# stm32f4x7v.net
KiCad netlist of a schematic drawn in Altium Designer
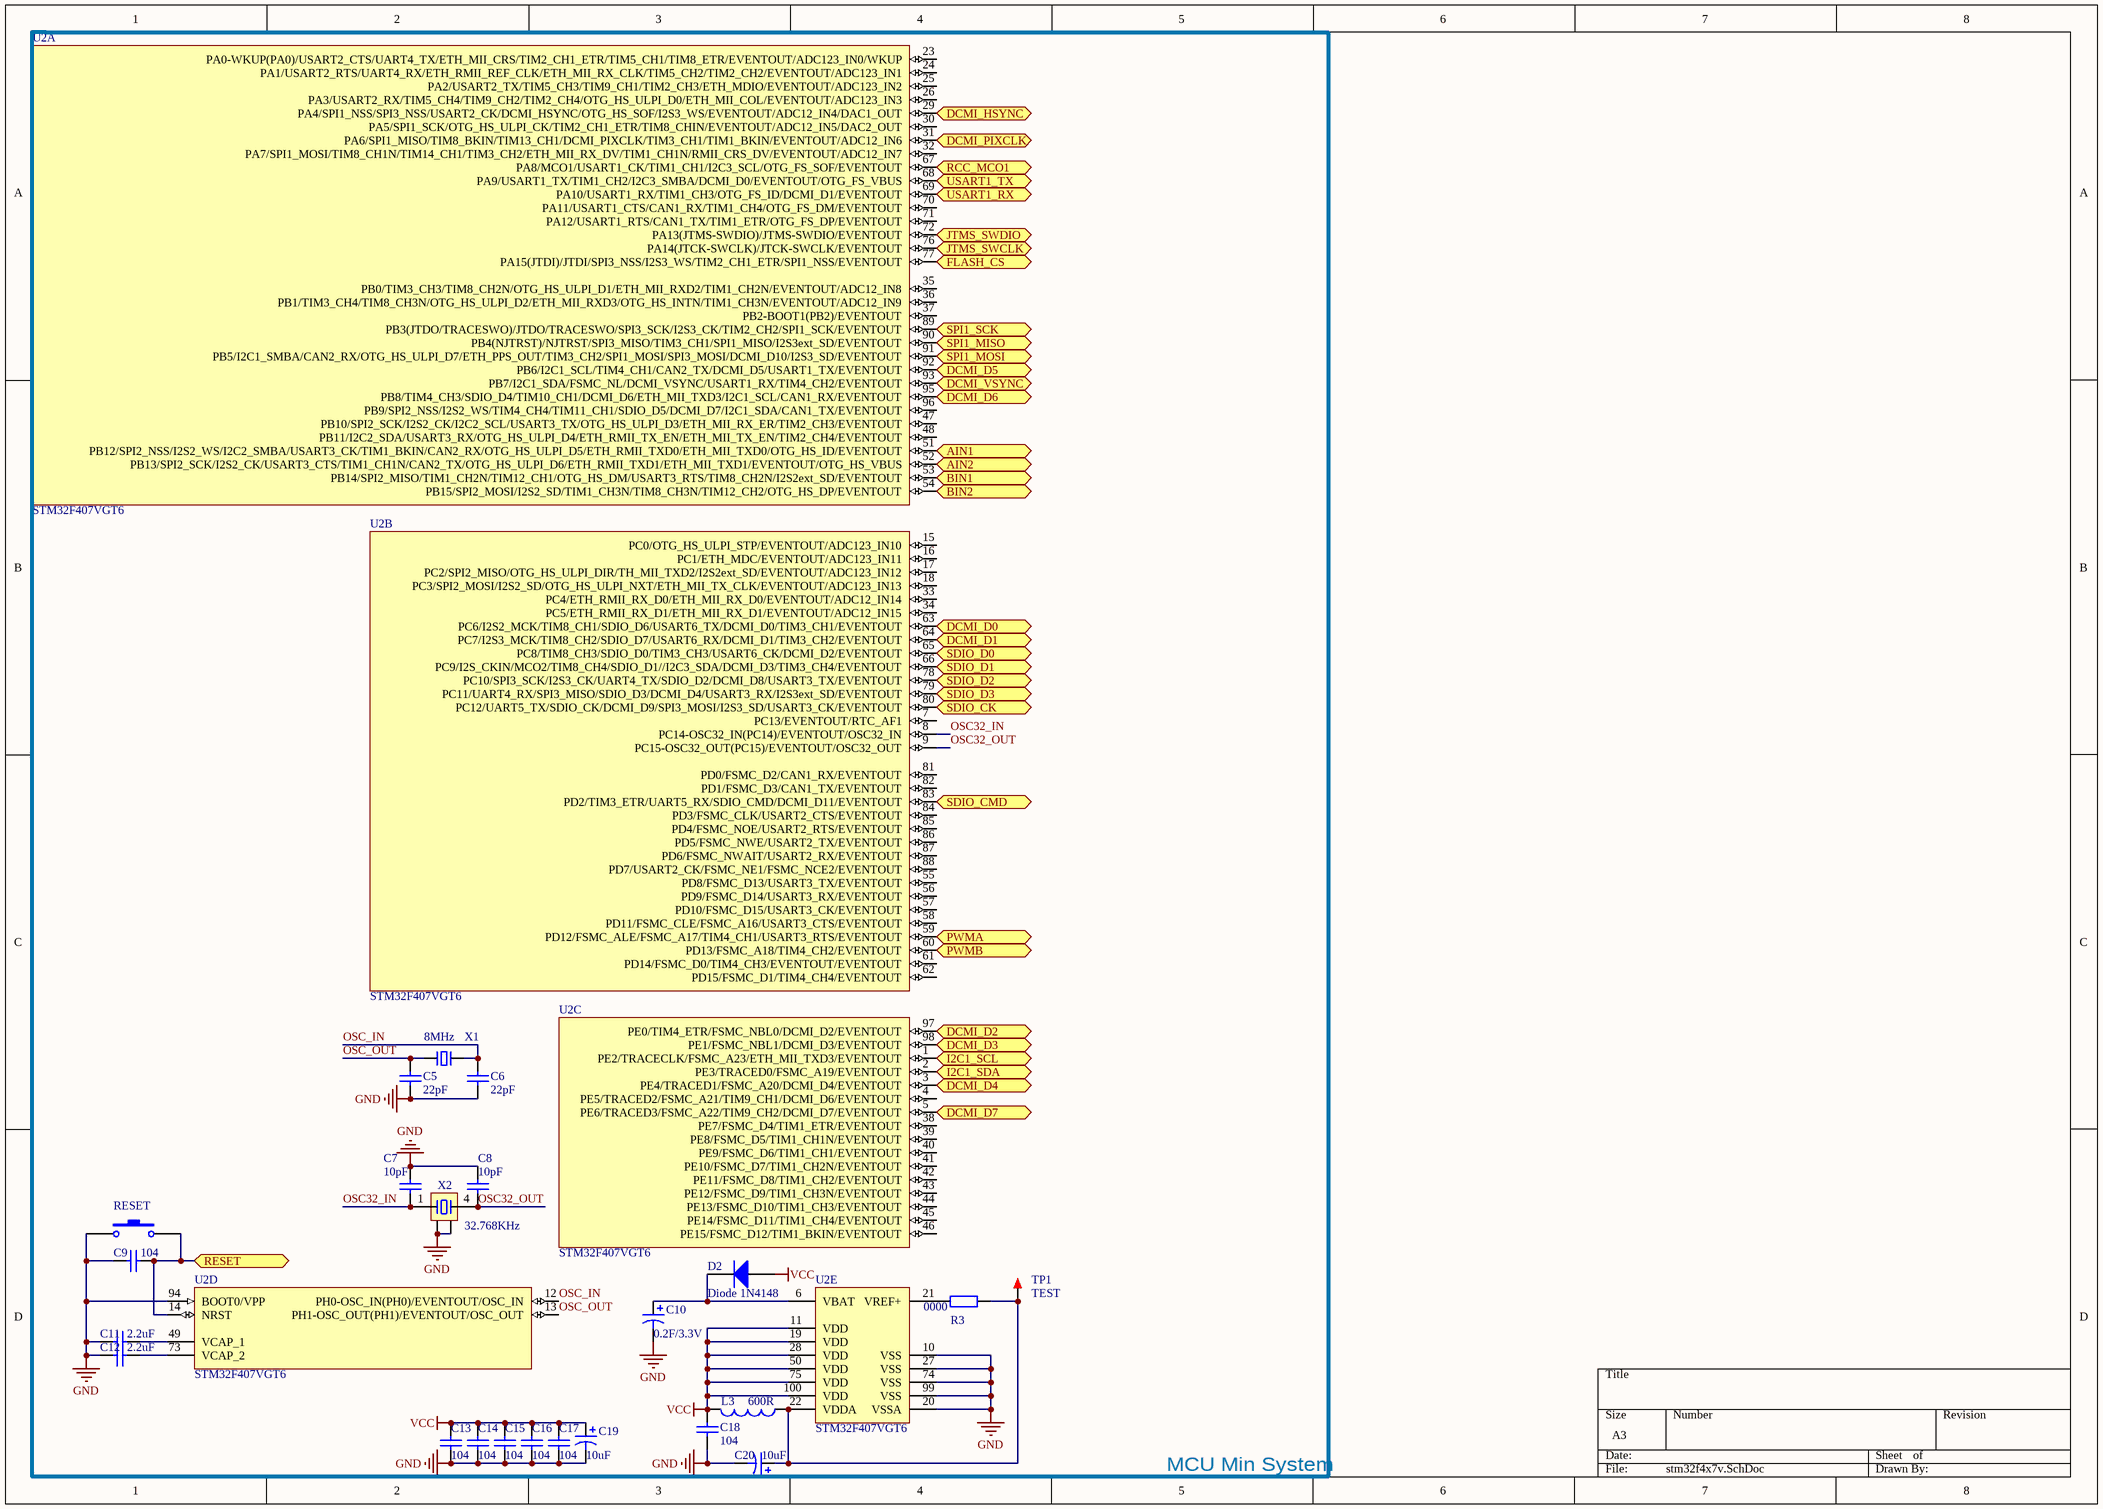
[diagram p0: stm32f4x7v.SchDoc]

(export (version "E")
  (design (tool "Eeschema 10.0.6"))
  (components
    (comp (ref "C5")
      (value "22pF")
      (footprint "C 0603_L")
      (description "Capacitor")
      (fields (field (name "PUBLISHER") "Altium Limited"))
      (libsource (lib "Miscellaneous Devices") (part "Cap"))
    )
    (comp (ref "C6")
      (value "22pF")
      (footprint "C 0603_L")
      (description "Capacitor")
      (fields (field (name "PUBLISHER") "Altium Limited"))
      (libsource (lib "Miscellaneous Devices") (part "Cap"))
    )
    (comp (ref "C7")
      (value "10pF")
      (footprint "C 0603_L")
      (description "Capacitor")
      (fields (field (name "PUBLISHER") "Altium Limited"))
      (libsource (lib "Miscellaneous Devices") (part "Cap"))
    )
    (comp (ref "C8")
      (value "10pF")
      (footprint "C 0603_L")
      (description "Capacitor")
      (fields (field (name "PUBLISHER") "Altium Limited"))
      (libsource (lib "Miscellaneous Devices") (part "Cap"))
    )
    (comp (ref "C9")
      (value "104")
      (footprint "C 0603_L")
      (description "Capacitor")
      (fields (field (name "PUBLISHER") "Altium Limited"))
      (libsource (lib "Miscellaneous Devices") (part "Cap"))
    )
    (comp (ref "C10")
      (value "0.2F/3.3V")
      (footprint "CD A(3216)")
      (description "Polarized Capacitor (Radial)")
      (fields (field (name "PUBLISHER") "Altium Limited"))
      (libsource (lib "Miscellaneous Devices") (part "Cap Pol1"))
    )
    (comp (ref "C11")
      (value "2.2uF")
      (footprint "C 0603_L")
      (description "Capacitor")
      (fields (field (name "PUBLISHER") "Altium Limited"))
      (libsource (lib "Miscellaneous Devices") (part "Cap"))
    )
    (comp (ref "C12")
      (value "2.2uF")
      (footprint "C 0603_L")
      (description "Capacitor")
      (fields (field (name "PUBLISHER") "Altium Limited"))
      (libsource (lib "Miscellaneous Devices") (part "Cap"))
    )
    (comp (ref "C13")
      (value "104")
      (footprint "C 0603_L")
      (description "Capacitor")
      (fields (field (name "PUBLISHER") "Altium Limited"))
      (libsource (lib "Miscellaneous Devices") (part "Cap"))
    )
    (comp (ref "C14")
      (value "104")
      (footprint "C 0603_L")
      (description "Capacitor")
      (fields (field (name "PUBLISHER") "Altium Limited"))
      (libsource (lib "Miscellaneous Devices") (part "Cap"))
    )
    (comp (ref "C15")
      (value "104")
      (footprint "C 0603_L")
      (description "Capacitor")
      (fields (field (name "PUBLISHER") "Altium Limited"))
      (libsource (lib "Miscellaneous Devices") (part "Cap"))
    )
    (comp (ref "C16")
      (value "104")
      (footprint "C 0603_L")
      (description "Capacitor")
      (fields (field (name "PUBLISHER") "Altium Limited"))
      (libsource (lib "Miscellaneous Devices") (part "Cap"))
    )
    (comp (ref "C17")
      (value "104")
      (footprint "C 0603_L")
      (description "Capacitor")
      (fields (field (name "PUBLISHER") "Altium Limited"))
      (libsource (lib "Miscellaneous Devices") (part "Cap"))
    )
    (comp (ref "C18")
      (value "104")
      (footprint "C 0603_L")
      (description "Capacitor")
      (fields (field (name "PUBLISHER") "Altium Limited"))
      (libsource (lib "Miscellaneous Devices") (part "Cap"))
    )
    (comp (ref "C19")
      (value "10uF")
      (footprint "CD A(3216)")
      (description "Polarized Capacitor (Radial)")
      (fields (field (name "PUBLISHER") "Altium Limited"))
      (libsource (lib "Miscellaneous Devices") (part "Cap Pol1"))
    )
    (comp (ref "C20")
      (value "10uF")
      (footprint "CD A(3216)")
      (description "Polarized Capacitor (Radial)")
      (fields (field (name "PUBLISHER") "Altium Limited"))
      (libsource (lib "Miscellaneous Devices") (part "Cap Pol1"))
    )
    (comp (ref "D2")
      (value "Diode 1N4148")
      (footprint "SOD-523")
      (description "High Conductance Fast Diode")
      (fields (field (name "PUBLISHER") "Altium Limited"))
      (libsource (lib "Miscellaneous Devices") (part "Diode 1N4148"))
    )
    (comp (ref "L3")
      (value "600R")
      (footprint "R 0603_L")
      (description "Inductor")
      (fields (field (name "PUBLISHER") "Altium Limited"))
      (libsource (lib "Miscellaneous Devices") (part "Inductor"))
    )
    (comp (ref "R3")
      (value "0000")
      (footprint "R 0603_L")
      (description "Resistor")
      (fields (field (name "PUBLISHER") "Altium Limited"))
      (libsource (lib "Miscellaneous Devices") (part "Res2"))
    )
    (comp (ref "RESET")
      (value "RESET")
      (footprint "micro button_2_SMD")
      (description "Switch")
      (fields (field (name "PUBLISHER") "Altium Limited"))
      (libsource (lib "Miscellaneous Devices") (part "SW-PB"))
    )
    (comp (ref "TP1")
      (value "TEST")
      (footprint "TEST 0.8")
      (description "测试点")
      (fields (field (name "版权归属") "源创客"))
      (libsource (lib "15.1 - 未分类器件") (part "TEST"))
    )
    (comp (ref "U2")
      (value "STM32F407VGT6")
      (footprint "LQFP100_V")
      (libsource (lib "STMicroelectronics STM32 F4") (part "STM32F407VGT6"))
    )
    (comp (ref "X1")
      (value "8MHz")
      (footprint "OSC 5032-2P")
      (description "2脚无源脚晶振")
      (fields (field (name "版权归属") "源创客"))
      (libsource (lib "10.1 - 保险丝-晶振") (part "XTAL-2P"))
    )
    (comp (ref "X2")
      (value "32.768KHz")
      (footprint "OSC MC-146")
      (description "MC系列4脚晶振")
      (fields (field (name "版权归属") "源创客"))
      (libsource (lib "10.1 - 保险丝-晶振") (part "XTAL-MC-4P"))
    )
  )
  (nets
    (net (code "1") (name "/AIN1") (class "Default")
      (node (ref "U2") (pin "51") (pinfunction "PB12/SPI2_NSS/I2S2_WS/I2C2_SMBA/USART3_CK/TIM1_BKIN/CAN2_RX/OTG_HS_ULPI_D5/ETH_RMII_TXD0/ETH_MII_TXD0/OTG_HS_ID/EVENTOUT_51") (pintype "bidirectional"))
    )
    (net (code "2") (name "/AIN2") (class "Default")
      (node (ref "U2") (pin "52") (pinfunction "PB13/SPI2_SCK/I2S2_CK/USART3_CTS/TIM1_CH1N/CAN2_TX/OTG_HS_ULPI_D6/ETH_RMII_TXD1/ETH_MII_TXD1/EVENTOUT/OTG_HS_VBUS_52") (pintype "bidirectional"))
    )
    (net (code "3") (name "/BIN1") (class "Default")
      (node (ref "U2") (pin "53") (pinfunction "PB14/SPI2_MISO/TIM1_CH2N/TIM12_CH1/OTG_HS_DM/USART3_RTS/TIM8_CH2N/I2S2ext_SD/EVENTOUT_53") (pintype "bidirectional"))
    )
    (net (code "4") (name "/BIN2") (class "Default")
      (node (ref "U2") (pin "54") (pinfunction "PB15/SPI2_MOSI/I2S2_SD/TIM1_CH3N/TIM8_CH3N/TIM12_CH2/OTG_HS_DP/EVENTOUT_54") (pintype "bidirectional"))
    )
    (net (code "5") (name "/DCMI_D0") (class "Default")
      (node (ref "U2") (pin "63") (pinfunction "PC6/I2S2_MCK/TIM8_CH1/SDIO_D6/USART6_TX/DCMI_D0/TIM3_CH1/EVENTOUT_63") (pintype "bidirectional"))
    )
    (net (code "6") (name "/DCMI_D1") (class "Default")
      (node (ref "U2") (pin "64") (pinfunction "PC7/I2S3_MCK/TIM8_CH2/SDIO_D7/USART6_RX/DCMI_D1/TIM3_CH2/EVENTOUT_64") (pintype "bidirectional"))
    )
    (net (code "7") (name "/DCMI_D2") (class "Default")
      (node (ref "U2") (pin "97") (pinfunction "PE0/TIM4_ETR/FSMC_NBL0/DCMI_D2/EVENTOUT_97") (pintype "bidirectional"))
    )
    (net (code "8") (name "/DCMI_D3") (class "Default")
      (node (ref "U2") (pin "98") (pinfunction "PE1/FSMC_NBL1/DCMI_D3/EVENTOUT_98") (pintype "bidirectional"))
    )
    (net (code "9") (name "/DCMI_D4") (class "Default")
      (node (ref "U2") (pin "3") (pinfunction "PE4/TRACED1/FSMC_A20/DCMI_D4/EVENTOUT_3") (pintype "bidirectional"))
    )
    (net (code "10") (name "/DCMI_D5") (class "Default")
      (node (ref "U2") (pin "92") (pinfunction "PB6/I2C1_SCL/TIM4_CH1/CAN2_TX/DCMI_D5/USART1_TX/EVENTOUT_92") (pintype "bidirectional"))
    )
    (net (code "11") (name "/DCMI_D6") (class "Default")
      (node (ref "U2") (pin "95") (pinfunction "PB8/TIM4_CH3/SDIO_D4/TIM10_CH1/DCMI_D6/ETH_MII_TXD3/I2C1_SCL/CAN1_RX/EVENTOUT_95") (pintype "bidirectional"))
    )
    (net (code "12") (name "/DCMI_D7") (class "Default")
      (node (ref "U2") (pin "5") (pinfunction "PE6/TRACED3/FSMC_A22/TIM9_CH2/DCMI_D7/EVENTOUT_5") (pintype "bidirectional"))
    )
    (net (code "13") (name "/DCMI_HSYNC") (class "Default")
      (node (ref "U2") (pin "29") (pinfunction "PA4/SPI1_NSS/SPI3_NSS/USART2_CK/DCMI_HSYNC/OTG_HS_SOF/I2S3_WS/EVENTOUT/ADC12_IN4/DAC1_OUT_29") (pintype "bidirectional"))
    )
    (net (code "14") (name "/DCMI_PIXCLK") (class "Default")
      (node (ref "U2") (pin "31") (pinfunction "PA6/SPI1_MISO/TIM8_BKIN/TIM13_CH1/DCMI_PIXCLK/TIM3_CH1/TIM1_BKIN/EVENTOUT/ADC12_IN6_31") (pintype "bidirectional"))
    )
    (net (code "15") (name "/DCMI_VSYNC") (class "Default")
      (node (ref "U2") (pin "93") (pinfunction "PB7/I2C1_SDA/FSMC_NL/DCMI_VSYNC/USART1_RX/TIM4_CH2/EVENTOUT_93") (pintype "bidirectional"))
    )
    (net (code "16") (name "/FLASH_CS") (class "Default")
      (node (ref "U2") (pin "77") (pinfunction "PA15(JTDI)/JTDI/SPI3_NSS/I2S3_WS/TIM2_CH1_ETR/SPI1_NSS/EVENTOUT_77") (pintype "bidirectional"))
    )
    (net (code "17") (name "/I2C1_SCL") (class "Default")
      (node (ref "U2") (pin "1") (pinfunction "PE2/TRACECLK/FSMC_A23/ETH_MII_TXD3/EVENTOUT_1") (pintype "bidirectional"))
    )
    (net (code "18") (name "/I2C1_SDA") (class "Default")
      (node (ref "U2") (pin "2") (pinfunction "PE3/TRACED0/FSMC_A19/EVENTOUT_2") (pintype "bidirectional"))
    )
    (net (code "19") (name "/JTMS_SWCLK") (class "Default")
      (node (ref "U2") (pin "76") (pinfunction "PA14(JTCK-SWCLK)/JTCK-SWCLK/EVENTOUT_76") (pintype "bidirectional"))
    )
    (net (code "20") (name "/JTMS_SWDIO") (class "Default")
      (node (ref "U2") (pin "72") (pinfunction "PA13(JTMS-SWDIO)/JTMS-SWDIO/EVENTOUT_72") (pintype "bidirectional"))
    )
    (net (code "21") (name "/OSC32_IN") (class "Default")
      (node (ref "C7") (pin "1") (pinfunction "1_1") (pintype "passive"))
      (node (ref "U2") (pin "8") (pinfunction "PC14-OSC32_IN(PC14)/EVENTOUT/OSC32_IN_8") (pintype "bidirectional"))
      (node (ref "X2") (pin "1") (pinfunction "1_1") (pintype "passive"))
    )
    (net (code "22") (name "/OSC32_OUT") (class "Default")
      (node (ref "C8") (pin "1") (pinfunction "1_1") (pintype "passive"))
      (node (ref "U2") (pin "9") (pinfunction "PC15-OSC32_OUT(PC15)/EVENTOUT/OSC32_OUT_9") (pintype "bidirectional"))
      (node (ref "X2") (pin "4") (pinfunction "4_4") (pintype "passive"))
    )
    (net (code "23") (name "/OSC_IN") (class "Default")
      (node (ref "C6") (pin "2") (pinfunction "2_2") (pintype "passive"))
      (node (ref "U2") (pin "12") (pinfunction "PH0-OSC_IN(PH0)/EVENTOUT/OSC_IN_12") (pintype "bidirectional"))
      (node (ref "X1") (pin "2") (pinfunction "2_2") (pintype "passive"))
    )
    (net (code "24") (name "/OSC_OUT") (class "Default")
      (node (ref "C5") (pin "2") (pinfunction "2_2") (pintype "passive"))
      (node (ref "U2") (pin "13") (pinfunction "PH1-OSC_OUT(PH1)/EVENTOUT/OSC_OUT_13") (pintype "bidirectional"))
      (node (ref "X1") (pin "1") (pinfunction "1_1") (pintype "passive"))
    )
    (net (code "25") (name "/PWMA") (class "Default")
      (node (ref "U2") (pin "59") (pinfunction "PD12/FSMC_ALE/FSMC_A17/TIM4_CH1/USART3_RTS/EVENTOUT_59") (pintype "bidirectional"))
    )
    (net (code "26") (name "/PWMB") (class "Default")
      (node (ref "U2") (pin "60") (pinfunction "PD13/FSMC_A18/TIM4_CH2/EVENTOUT_60") (pintype "bidirectional"))
    )
    (net (code "27") (name "/RCC_MCO1") (class "Default")
      (node (ref "U2") (pin "67") (pinfunction "PA8/MCO1/USART1_CK/TIM1_CH1/I2C3_SCL/OTG_FS_SOF/EVENTOUT_67") (pintype "bidirectional"))
    )
    (net (code "28") (name "/RESET") (class "Default")
      (node (ref "C9") (pin "2") (pinfunction "2_2") (pintype "passive"))
      (node (ref "RESET") (pin "2") (pinfunction "2_2") (pintype "passive"))
      (node (ref "U2") (pin "14") (pinfunction "NRST_14") (pintype "bidirectional"))
    )
    (net (code "29") (name "/SDIO_CK") (class "Default")
      (node (ref "U2") (pin "80") (pinfunction "PC12/UART5_TX/SDIO_CK/DCMI_D9/SPI3_MOSI/I2S3_SD/USART3_CK/EVENTOUT_80") (pintype "bidirectional"))
    )
    (net (code "30") (name "/SDIO_CMD") (class "Default")
      (node (ref "U2") (pin "83") (pinfunction "PD2/TIM3_ETR/UART5_RX/SDIO_CMD/DCMI_D11/EVENTOUT_83") (pintype "bidirectional"))
    )
    (net (code "31") (name "/SDIO_D0") (class "Default")
      (node (ref "U2") (pin "65") (pinfunction "PC8/TIM8_CH3/SDIO_D0/TIM3_CH3/USART6_CK/DCMI_D2/EVENTOUT_65") (pintype "bidirectional"))
    )
    (net (code "32") (name "/SDIO_D1") (class "Default")
      (node (ref "U2") (pin "66") (pinfunction "PC9/I2S_CKIN/MCO2/TIM8_CH4/SDIO_D1//I2C3_SDA/DCMI_D3/TIM3_CH4/EVENTOUT_66") (pintype "bidirectional"))
    )
    (net (code "33") (name "/SDIO_D2") (class "Default")
      (node (ref "U2") (pin "78") (pinfunction "PC10/SPI3_SCK/I2S3_CK/UART4_TX/SDIO_D2/DCMI_D8/USART3_TX/EVENTOUT_78") (pintype "bidirectional"))
    )
    (net (code "34") (name "/SDIO_D3") (class "Default")
      (node (ref "U2") (pin "79") (pinfunction "PC11/UART4_RX/SPI3_MISO/SDIO_D3/DCMI_D4/USART3_RX/I2S3ext_SD/EVENTOUT_79") (pintype "bidirectional"))
    )
    (net (code "35") (name "/SPI1_MISO") (class "Default")
      (node (ref "U2") (pin "90") (pinfunction "PB4(NJTRST)/NJTRST/SPI3_MISO/TIM3_CH1/SPI1_MISO/I2S3ext_SD/EVENTOUT_90") (pintype "bidirectional"))
    )
    (net (code "36") (name "/SPI1_MOSI") (class "Default")
      (node (ref "U2") (pin "91") (pinfunction "PB5/I2C1_SMBA/CAN2_RX/OTG_HS_ULPI_D7/ETH_PPS_OUT/TIM3_CH2/SPI1_MOSI/SPI3_MOSI/DCMI_D10/I2S3_SD/EVENTOUT_91") (pintype "bidirectional"))
    )
    (net (code "37") (name "/SPI1_SCK") (class "Default")
      (node (ref "U2") (pin "89") (pinfunction "PB3(JTDO/TRACESWO)/JTDO/TRACESWO/SPI3_SCK/I2S3_CK/TIM2_CH2/SPI1_SCK/EVENTOUT_89") (pintype "bidirectional"))
    )
    (net (code "38") (name "/USART1_RX") (class "Default")
      (node (ref "U2") (pin "69") (pinfunction "PA10/USART1_RX/TIM1_CH3/OTG_FS_ID/DCMI_D1/EVENTOUT_69") (pintype "bidirectional"))
    )
    (net (code "39") (name "/USART1_TX") (class "Default")
      (node (ref "U2") (pin "68") (pinfunction "PA9/USART1_TX/TIM1_CH2/I2C3_SMBA/DCMI_D0/EVENTOUT/OTG_FS_VBUS_68") (pintype "bidirectional"))
    )
    (net (code "40") (name "GND") (class "Default")
      (node (ref "C10") (pin "2") (pinfunction "2_2") (pintype "passive"))
      (node (ref "C11") (pin "1") (pinfunction "1_1") (pintype "passive"))
      (node (ref "C12") (pin "1") (pinfunction "1_1") (pintype "passive"))
      (node (ref "C13") (pin "1") (pinfunction "1_1") (pintype "passive"))
      (node (ref "C14") (pin "1") (pinfunction "1_1") (pintype "passive"))
      (node (ref "C15") (pin "1") (pinfunction "1_1") (pintype "passive"))
      (node (ref "C16") (pin "1") (pinfunction "1_1") (pintype "passive"))
      (node (ref "C17") (pin "1") (pinfunction "1_1") (pintype "passive"))
      (node (ref "C18") (pin "1") (pinfunction "1_1") (pintype "passive"))
      (node (ref "C19") (pin "2") (pinfunction "2_2") (pintype "passive"))
      (node (ref "C20") (pin "2") (pinfunction "2_2") (pintype "passive"))
      (node (ref "C5") (pin "1") (pinfunction "1_1") (pintype "passive"))
      (node (ref "C6") (pin "1") (pinfunction "1_1") (pintype "passive"))
      (node (ref "C7") (pin "2") (pinfunction "2_2") (pintype "passive"))
      (node (ref "C8") (pin "2") (pinfunction "2_2") (pintype "passive"))
      (node (ref "C9") (pin "1") (pinfunction "1_1") (pintype "passive"))
      (node (ref "RESET") (pin "1") (pinfunction "1_1") (pintype "passive"))
      (node (ref "U2") (pin "10") (pinfunction "VSS_10") (pintype "power_in"))
      (node (ref "U2") (pin "20") (pinfunction "VSSA_20") (pintype "power_in"))
      (node (ref "U2") (pin "27") (pinfunction "VSS_27") (pintype "power_in"))
      (node (ref "U2") (pin "74") (pinfunction "VSS_74") (pintype "power_in"))
      (node (ref "U2") (pin "94") (pinfunction "BOOT0/VPP_94") (pintype "input"))
      (node (ref "U2") (pin "99") (pinfunction "VSS_99") (pintype "power_in"))
      (node (ref "X2") (pin "2") (pinfunction "2_2") (pintype "passive"))
      (node (ref "X2") (pin "3") (pinfunction "3_3") (pintype "passive"))
    )
    (net (code "41") (name "Net-(D2-K)") (class "Default")
      (node (ref "C10") (pin "1") (pinfunction "1_1") (pintype "passive"))
      (node (ref "D2") (pin "2") (pinfunction "K_2") (pintype "passive"))
      (node (ref "U2") (pin "6") (pinfunction "VBAT_6") (pintype "power_in"))
    )
    (net (code "42") (name "Net-(U2D-VCAP_1)") (class "Default")
      (node (ref "C11") (pin "2") (pinfunction "2_2") (pintype "passive"))
      (node (ref "U2") (pin "49") (pinfunction "VCAP_1_49") (pintype "power_in"))
    )
    (net (code "43") (name "Net-(U2D-VCAP_2)") (class "Default")
      (node (ref "C12") (pin "2") (pinfunction "2_2") (pintype "passive"))
      (node (ref "U2") (pin "73") (pinfunction "VCAP_2_73") (pintype "power_in"))
    )
    (net (code "44") (name "Net-(U2E-VDDA)") (class "Default")
      (node (ref "C20") (pin "1") (pinfunction "1_1") (pintype "passive"))
      (node (ref "L3") (pin "1") (pinfunction "1_1") (pintype "passive"))
      (node (ref "R3") (pin "1") (pinfunction "1_1") (pintype "passive"))
      (node (ref "TP1") (pin "1") (pinfunction "1_1") (pintype "passive"))
      (node (ref "U2") (pin "22") (pinfunction "VDDA_22") (pintype "power_in"))
    )
    (net (code "45") (name "Net-(U2E-VREF+)") (class "Default")
      (node (ref "R3") (pin "2") (pinfunction "2_2") (pintype "passive"))
      (node (ref "U2") (pin "21") (pinfunction "VREF+_21") (pintype "power_in"))
    )
    (net (code "46") (name "VCC") (class "Default")
      (node (ref "C13") (pin "2") (pinfunction "2_2") (pintype "passive"))
      (node (ref "C14") (pin "2") (pinfunction "2_2") (pintype "passive"))
      (node (ref "C15") (pin "2") (pinfunction "2_2") (pintype "passive"))
      (node (ref "C16") (pin "2") (pinfunction "2_2") (pintype "passive"))
      (node (ref "C17") (pin "2") (pinfunction "2_2") (pintype "passive"))
      (node (ref "C18") (pin "2") (pinfunction "2_2") (pintype "passive"))
      (node (ref "C19") (pin "1") (pinfunction "1_1") (pintype "passive"))
      (node (ref "D2") (pin "1") (pinfunction "A_1") (pintype "passive"))
      (node (ref "L3") (pin "2") (pinfunction "2_2") (pintype "passive"))
      (node (ref "U2") (pin "100") (pinfunction "VDD_100") (pintype "power_in"))
      (node (ref "U2") (pin "11") (pinfunction "VDD_11") (pintype "power_in"))
      (node (ref "U2") (pin "19") (pinfunction "VDD_19") (pintype "power_in"))
      (node (ref "U2") (pin "28") (pinfunction "VDD_28") (pintype "power_in"))
      (node (ref "U2") (pin "50") (pinfunction "VDD_50") (pintype "power_in"))
      (node (ref "U2") (pin "75") (pinfunction "VDD_75") (pintype "power_in"))
    )
    (net (code "47") (name "unconnected-(U2A-PA0-WKUP(PA0){slash}USART2_CTS{slash}UART4_TX{slash}ETH_MII_CRS{slash}TIM2_CH1_ETR{slash}TIM5_CH1{slash}TIM8_ETR{slash}EVENTOUT{slash}ADC123_IN0{slash}WKUP-Pad23)") (class "Default")
      (node (ref "U2") (pin "23") (pinfunction "PA0-WKUP(PA0)/USART2_CTS/UART4_TX/ETH_MII_CRS/TIM2_CH1_ETR/TIM5_CH1/TIM8_ETR/EVENTOUT/ADC123_IN0/WKUP_23") (pintype "bidirectional"))
    )
    (net (code "48") (name "unconnected-(U2A-PA1{slash}USART2_RTS{slash}UART4_RX{slash}ETH_RMII_REF_CLK{slash}ETH_MII_RX_CLK{slash}TIM5_CH2{slash}TIM2_CH2{slash}EVENTOUT{slash}ADC123_IN1-Pad24)") (class "Default")
      (node (ref "U2") (pin "24") (pinfunction "PA1/USART2_RTS/UART4_RX/ETH_RMII_REF_CLK/ETH_MII_RX_CLK/TIM5_CH2/TIM2_CH2/EVENTOUT/ADC123_IN1_24") (pintype "bidirectional"))
    )
    (net (code "49") (name "unconnected-(U2A-PA2{slash}USART2_TX{slash}TIM5_CH3{slash}TIM9_CH1{slash}TIM2_CH3{slash}ETH_MDIO{slash}EVENTOUT{slash}ADC123_IN2-Pad25)") (class "Default")
      (node (ref "U2") (pin "25") (pinfunction "PA2/USART2_TX/TIM5_CH3/TIM9_CH1/TIM2_CH3/ETH_MDIO/EVENTOUT/ADC123_IN2_25") (pintype "bidirectional"))
    )
    (net (code "50") (name "unconnected-(U2A-PA3{slash}USART2_RX{slash}TIM5_CH4{slash}TIM9_CH2{slash}TIM2_CH4{slash}OTG_HS_ULPI_D0{slash}ETH_MII_COL{slash}EVENTOUT{slash}ADC123_IN3-Pad26)") (class "Default")
      (node (ref "U2") (pin "26") (pinfunction "PA3/USART2_RX/TIM5_CH4/TIM9_CH2/TIM2_CH4/OTG_HS_ULPI_D0/ETH_MII_COL/EVENTOUT/ADC123_IN3_26") (pintype "bidirectional"))
    )
    (net (code "51") (name "unconnected-(U2A-PA5{slash}SPI1_SCK{slash}OTG_HS_ULPI_CK{slash}TIM2_CH1_ETR{slash}TIM8_CHIN{slash}EVENTOUT{slash}ADC12_IN5{slash}DAC2_OUT-Pad30)") (class "Default")
      (node (ref "U2") (pin "30") (pinfunction "PA5/SPI1_SCK/OTG_HS_ULPI_CK/TIM2_CH1_ETR/TIM8_CHIN/EVENTOUT/ADC12_IN5/DAC2_OUT_30") (pintype "bidirectional"))
    )
    (net (code "52") (name "unconnected-(U2A-PA7{slash}SPI1_MOSI{slash}TIM8_CH1N{slash}TIM14_CH1{slash}TIM3_CH2{slash}ETH_MII_RX_DV{slash}TIM1_CH1N{slash}RMII_CRS_DV{slash}EVENTOUT{slash}ADC12_IN7-Pad32)") (class "Default")
      (node (ref "U2") (pin "32") (pinfunction "PA7/SPI1_MOSI/TIM8_CH1N/TIM14_CH1/TIM3_CH2/ETH_MII_RX_DV/TIM1_CH1N/RMII_CRS_DV/EVENTOUT/ADC12_IN7_32") (pintype "bidirectional"))
    )
    (net (code "53") (name "unconnected-(U2A-PA11{slash}USART1_CTS{slash}CAN1_RX{slash}TIM1_CH4{slash}OTG_FS_DM{slash}EVENTOUT-Pad70)") (class "Default")
      (node (ref "U2") (pin "70") (pinfunction "PA11/USART1_CTS/CAN1_RX/TIM1_CH4/OTG_FS_DM/EVENTOUT_70") (pintype "bidirectional"))
    )
    (net (code "54") (name "unconnected-(U2A-PA12{slash}USART1_RTS{slash}CAN1_TX{slash}TIM1_ETR{slash}OTG_FS_DP{slash}EVENTOUT-Pad71)") (class "Default")
      (node (ref "U2") (pin "71") (pinfunction "PA12/USART1_RTS/CAN1_TX/TIM1_ETR/OTG_FS_DP/EVENTOUT_71") (pintype "bidirectional"))
    )
    (net (code "55") (name "unconnected-(U2A-PB0{slash}TIM3_CH3{slash}TIM8_CH2N{slash}OTG_HS_ULPI_D1{slash}ETH_MII_RXD2{slash}TIM1_CH2N{slash}EVENTOUT{slash}ADC12_IN8-Pad35)") (class "Default")
      (node (ref "U2") (pin "35") (pinfunction "PB0/TIM3_CH3/TIM8_CH2N/OTG_HS_ULPI_D1/ETH_MII_RXD2/TIM1_CH2N/EVENTOUT/ADC12_IN8_35") (pintype "bidirectional"))
    )
    (net (code "56") (name "unconnected-(U2A-PB1{slash}TIM3_CH4{slash}TIM8_CH3N{slash}OTG_HS_ULPI_D2{slash}ETH_MII_RXD3{slash}OTG_HS_INTN{slash}TIM1_CH3N{slash}EVENTOUT{slash}ADC12_IN9-Pad36)") (class "Default")
      (node (ref "U2") (pin "36") (pinfunction "PB1/TIM3_CH4/TIM8_CH3N/OTG_HS_ULPI_D2/ETH_MII_RXD3/OTG_HS_INTN/TIM1_CH3N/EVENTOUT/ADC12_IN9_36") (pintype "bidirectional"))
    )
    (net (code "57") (name "unconnected-(U2A-PB2-BOOT1(PB2){slash}EVENTOUT-Pad37)") (class "Default")
      (node (ref "U2") (pin "37") (pinfunction "PB2-BOOT1(PB2)/EVENTOUT_37") (pintype "bidirectional"))
    )
    (net (code "58") (name "unconnected-(U2A-PB9{slash}SPI2_NSS{slash}I2S2_WS{slash}TIM4_CH4{slash}TIM11_CH1{slash}SDIO_D5{slash}DCMI_D7{slash}I2C1_SDA{slash}CAN1_TX{slash}EVENTOUT-Pad96)") (class "Default")
      (node (ref "U2") (pin "96") (pinfunction "PB9/SPI2_NSS/I2S2_WS/TIM4_CH4/TIM11_CH1/SDIO_D5/DCMI_D7/I2C1_SDA/CAN1_TX/EVENTOUT_96") (pintype "bidirectional"))
    )
    (net (code "59") (name "unconnected-(U2A-PB10{slash}SPI2_SCK{slash}I2S2_CK{slash}I2C2_SCL{slash}USART3_TX{slash}OTG_HS_ULPI_D3{slash}ETH_MII_RX_ER{slash}TIM2_CH3{slash}EVENTOUT-Pad47)") (class "Default")
      (node (ref "U2") (pin "47") (pinfunction "PB10/SPI2_SCK/I2S2_CK/I2C2_SCL/USART3_TX/OTG_HS_ULPI_D3/ETH_MII_RX_ER/TIM2_CH3/EVENTOUT_47") (pintype "bidirectional"))
    )
    (net (code "60") (name "unconnected-(U2A-PB11{slash}I2C2_SDA{slash}USART3_RX{slash}OTG_HS_ULPI_D4{slash}ETH_RMII_TX_EN{slash}ETH_MII_TX_EN{slash}TIM2_CH4{slash}EVENTOUT-Pad48)") (class "Default")
      (node (ref "U2") (pin "48") (pinfunction "PB11/I2C2_SDA/USART3_RX/OTG_HS_ULPI_D4/ETH_RMII_TX_EN/ETH_MII_TX_EN/TIM2_CH4/EVENTOUT_48") (pintype "bidirectional"))
    )
    (net (code "61") (name "unconnected-(U2B-PC0{slash}OTG_HS_ULPI_STP{slash}EVENTOUT{slash}ADC123_IN10-Pad15)") (class "Default")
      (node (ref "U2") (pin "15") (pinfunction "PC0/OTG_HS_ULPI_STP/EVENTOUT/ADC123_IN10_15") (pintype "bidirectional"))
    )
    (net (code "62") (name "unconnected-(U2B-PC1{slash}ETH_MDC{slash}EVENTOUT{slash}ADC123_IN11-Pad16)") (class "Default")
      (node (ref "U2") (pin "16") (pinfunction "PC1/ETH_MDC/EVENTOUT/ADC123_IN11_16") (pintype "bidirectional"))
    )
    (net (code "63") (name "unconnected-(U2B-PC2{slash}SPI2_MISO{slash}OTG_HS_ULPI_DIR{slash}TH_MII_TXD2{slash}I2S2ext_SD{slash}EVENTOUT{slash}ADC123_IN12-Pad17)") (class "Default")
      (node (ref "U2") (pin "17") (pinfunction "PC2/SPI2_MISO/OTG_HS_ULPI_DIR/TH_MII_TXD2/I2S2ext_SD/EVENTOUT/ADC123_IN12_17") (pintype "bidirectional"))
    )
    (net (code "64") (name "unconnected-(U2B-PC3{slash}SPI2_MOSI{slash}I2S2_SD{slash}OTG_HS_ULPI_NXT{slash}ETH_MII_TX_CLK{slash}EVENTOUT{slash}ADC123_IN13-Pad18)") (class "Default")
      (node (ref "U2") (pin "18") (pinfunction "PC3/SPI2_MOSI/I2S2_SD/OTG_HS_ULPI_NXT/ETH_MII_TX_CLK/EVENTOUT/ADC123_IN13_18") (pintype "bidirectional"))
    )
    (net (code "65") (name "unconnected-(U2B-PC4{slash}ETH_RMII_RX_D0{slash}ETH_MII_RX_D0{slash}EVENTOUT{slash}ADC12_IN14-Pad33)") (class "Default")
      (node (ref "U2") (pin "33") (pinfunction "PC4/ETH_RMII_RX_D0/ETH_MII_RX_D0/EVENTOUT/ADC12_IN14_33") (pintype "bidirectional"))
    )
    (net (code "66") (name "unconnected-(U2B-PC5{slash}ETH_RMII_RX_D1{slash}ETH_MII_RX_D1{slash}EVENTOUT{slash}ADC12_IN15-Pad34)") (class "Default")
      (node (ref "U2") (pin "34") (pinfunction "PC5/ETH_RMII_RX_D1/ETH_MII_RX_D1/EVENTOUT/ADC12_IN15_34") (pintype "bidirectional"))
    )
    (net (code "67") (name "unconnected-(U2B-PC13{slash}EVENTOUT{slash}RTC_AF1-Pad7)") (class "Default")
      (node (ref "U2") (pin "7") (pinfunction "PC13/EVENTOUT/RTC_AF1_7") (pintype "bidirectional"))
    )
    (net (code "68") (name "unconnected-(U2B-PD0{slash}FSMC_D2{slash}CAN1_RX{slash}EVENTOUT-Pad81)") (class "Default")
      (node (ref "U2") (pin "81") (pinfunction "PD0/FSMC_D2/CAN1_RX/EVENTOUT_81") (pintype "bidirectional"))
    )
    (net (code "69") (name "unconnected-(U2B-PD1{slash}FSMC_D3{slash}CAN1_TX{slash}EVENTOUT-Pad82)") (class "Default")
      (node (ref "U2") (pin "82") (pinfunction "PD1/FSMC_D3/CAN1_TX/EVENTOUT_82") (pintype "bidirectional"))
    )
    (net (code "70") (name "unconnected-(U2B-PD3{slash}FSMC_CLK{slash}USART2_CTS{slash}EVENTOUT-Pad84)") (class "Default")
      (node (ref "U2") (pin "84") (pinfunction "PD3/FSMC_CLK/USART2_CTS/EVENTOUT_84") (pintype "bidirectional"))
    )
    (net (code "71") (name "unconnected-(U2B-PD4{slash}FSMC_NOE{slash}USART2_RTS{slash}EVENTOUT-Pad85)") (class "Default")
      (node (ref "U2") (pin "85") (pinfunction "PD4/FSMC_NOE/USART2_RTS/EVENTOUT_85") (pintype "bidirectional"))
    )
    (net (code "72") (name "unconnected-(U2B-PD5{slash}FSMC_NWE{slash}USART2_TX{slash}EVENTOUT-Pad86)") (class "Default")
      (node (ref "U2") (pin "86") (pinfunction "PD5/FSMC_NWE/USART2_TX/EVENTOUT_86") (pintype "bidirectional"))
    )
    (net (code "73") (name "unconnected-(U2B-PD6{slash}FSMC_NWAIT{slash}USART2_RX{slash}EVENTOUT-Pad87)") (class "Default")
      (node (ref "U2") (pin "87") (pinfunction "PD6/FSMC_NWAIT/USART2_RX/EVENTOUT_87") (pintype "bidirectional"))
    )
    (net (code "74") (name "unconnected-(U2B-PD7{slash}USART2_CK{slash}FSMC_NE1{slash}FSMC_NCE2{slash}EVENTOUT-Pad88)") (class "Default")
      (node (ref "U2") (pin "88") (pinfunction "PD7/USART2_CK/FSMC_NE1/FSMC_NCE2/EVENTOUT_88") (pintype "bidirectional"))
    )
    (net (code "75") (name "unconnected-(U2B-PD8{slash}FSMC_D13{slash}USART3_TX{slash}EVENTOUT-Pad55)") (class "Default")
      (node (ref "U2") (pin "55") (pinfunction "PD8/FSMC_D13/USART3_TX/EVENTOUT_55") (pintype "bidirectional"))
    )
    (net (code "76") (name "unconnected-(U2B-PD9{slash}FSMC_D14{slash}USART3_RX{slash}EVENTOUT-Pad56)") (class "Default")
      (node (ref "U2") (pin "56") (pinfunction "PD9/FSMC_D14/USART3_RX/EVENTOUT_56") (pintype "bidirectional"))
    )
    (net (code "77") (name "unconnected-(U2B-PD10{slash}FSMC_D15{slash}USART3_CK{slash}EVENTOUT-Pad57)") (class "Default")
      (node (ref "U2") (pin "57") (pinfunction "PD10/FSMC_D15/USART3_CK/EVENTOUT_57") (pintype "bidirectional"))
    )
    (net (code "78") (name "unconnected-(U2B-PD11{slash}FSMC_CLE{slash}FSMC_A16{slash}USART3_CTS{slash}EVENTOUT-Pad58)") (class "Default")
      (node (ref "U2") (pin "58") (pinfunction "PD11/FSMC_CLE/FSMC_A16/USART3_CTS/EVENTOUT_58") (pintype "bidirectional"))
    )
    (net (code "79") (name "unconnected-(U2B-PD14{slash}FSMC_D0{slash}TIM4_CH3{slash}EVENTOUT{slash}EVENTOUT-Pad61)") (class "Default")
      (node (ref "U2") (pin "61") (pinfunction "PD14/FSMC_D0/TIM4_CH3/EVENTOUT/EVENTOUT_61") (pintype "bidirectional"))
    )
    (net (code "80") (name "unconnected-(U2B-PD15{slash}FSMC_D1{slash}TIM4_CH4{slash}EVENTOUT-Pad62)") (class "Default")
      (node (ref "U2") (pin "62") (pinfunction "PD15/FSMC_D1/TIM4_CH4/EVENTOUT_62") (pintype "bidirectional"))
    )
    (net (code "81") (name "unconnected-(U2C-PE5{slash}TRACED2{slash}FSMC_A21{slash}TIM9_CH1{slash}DCMI_D6{slash}EVENTOUT-Pad4)") (class "Default")
      (node (ref "U2") (pin "4") (pinfunction "PE5/TRACED2/FSMC_A21/TIM9_CH1/DCMI_D6/EVENTOUT_4") (pintype "bidirectional"))
    )
    (net (code "82") (name "unconnected-(U2C-PE7{slash}FSMC_D4{slash}TIM1_ETR{slash}EVENTOUT-Pad38)") (class "Default")
      (node (ref "U2") (pin "38") (pinfunction "PE7/FSMC_D4/TIM1_ETR/EVENTOUT_38") (pintype "bidirectional"))
    )
    (net (code "83") (name "unconnected-(U2C-PE8{slash}FSMC_D5{slash}TIM1_CH1N{slash}EVENTOUT-Pad39)") (class "Default")
      (node (ref "U2") (pin "39") (pinfunction "PE8/FSMC_D5/TIM1_CH1N/EVENTOUT_39") (pintype "bidirectional"))
    )
    (net (code "84") (name "unconnected-(U2C-PE9{slash}FSMC_D6{slash}TIM1_CH1{slash}EVENTOUT-Pad40)") (class "Default")
      (node (ref "U2") (pin "40") (pinfunction "PE9/FSMC_D6/TIM1_CH1/EVENTOUT_40") (pintype "bidirectional"))
    )
    (net (code "85") (name "unconnected-(U2C-PE10{slash}FSMC_D7{slash}TIM1_CH2N{slash}EVENTOUT-Pad41)") (class "Default")
      (node (ref "U2") (pin "41") (pinfunction "PE10/FSMC_D7/TIM1_CH2N/EVENTOUT_41") (pintype "bidirectional"))
    )
    (net (code "86") (name "unconnected-(U2C-PE11{slash}FSMC_D8{slash}TIM1_CH2{slash}EVENTOUT-Pad42)") (class "Default")
      (node (ref "U2") (pin "42") (pinfunction "PE11/FSMC_D8/TIM1_CH2/EVENTOUT_42") (pintype "bidirectional"))
    )
    (net (code "87") (name "unconnected-(U2C-PE12{slash}FSMC_D9{slash}TIM1_CH3N{slash}EVENTOUT-Pad43)") (class "Default")
      (node (ref "U2") (pin "43") (pinfunction "PE12/FSMC_D9/TIM1_CH3N/EVENTOUT_43") (pintype "bidirectional"))
    )
    (net (code "88") (name "unconnected-(U2C-PE13{slash}FSMC_D10{slash}TIM1_CH3{slash}EVENTOUT-Pad44)") (class "Default")
      (node (ref "U2") (pin "44") (pinfunction "PE13/FSMC_D10/TIM1_CH3/EVENTOUT_44") (pintype "bidirectional"))
    )
    (net (code "89") (name "unconnected-(U2C-PE14{slash}FSMC_D11{slash}TIM1_CH4{slash}EVENTOUT-Pad45)") (class "Default")
      (node (ref "U2") (pin "45") (pinfunction "PE14/FSMC_D11/TIM1_CH4/EVENTOUT_45") (pintype "bidirectional"))
    )
    (net (code "90") (name "unconnected-(U2C-PE15{slash}FSMC_D12{slash}TIM1_BKIN{slash}EVENTOUT-Pad46)") (class "Default")
      (node (ref "U2") (pin "46") (pinfunction "PE15/FSMC_D12/TIM1_BKIN/EVENTOUT_46") (pintype "bidirectional"))
    )
  )
)
